# Smart_Podium_Circuit.net
KiCad netlist of a schematic drawn in Altium Designer
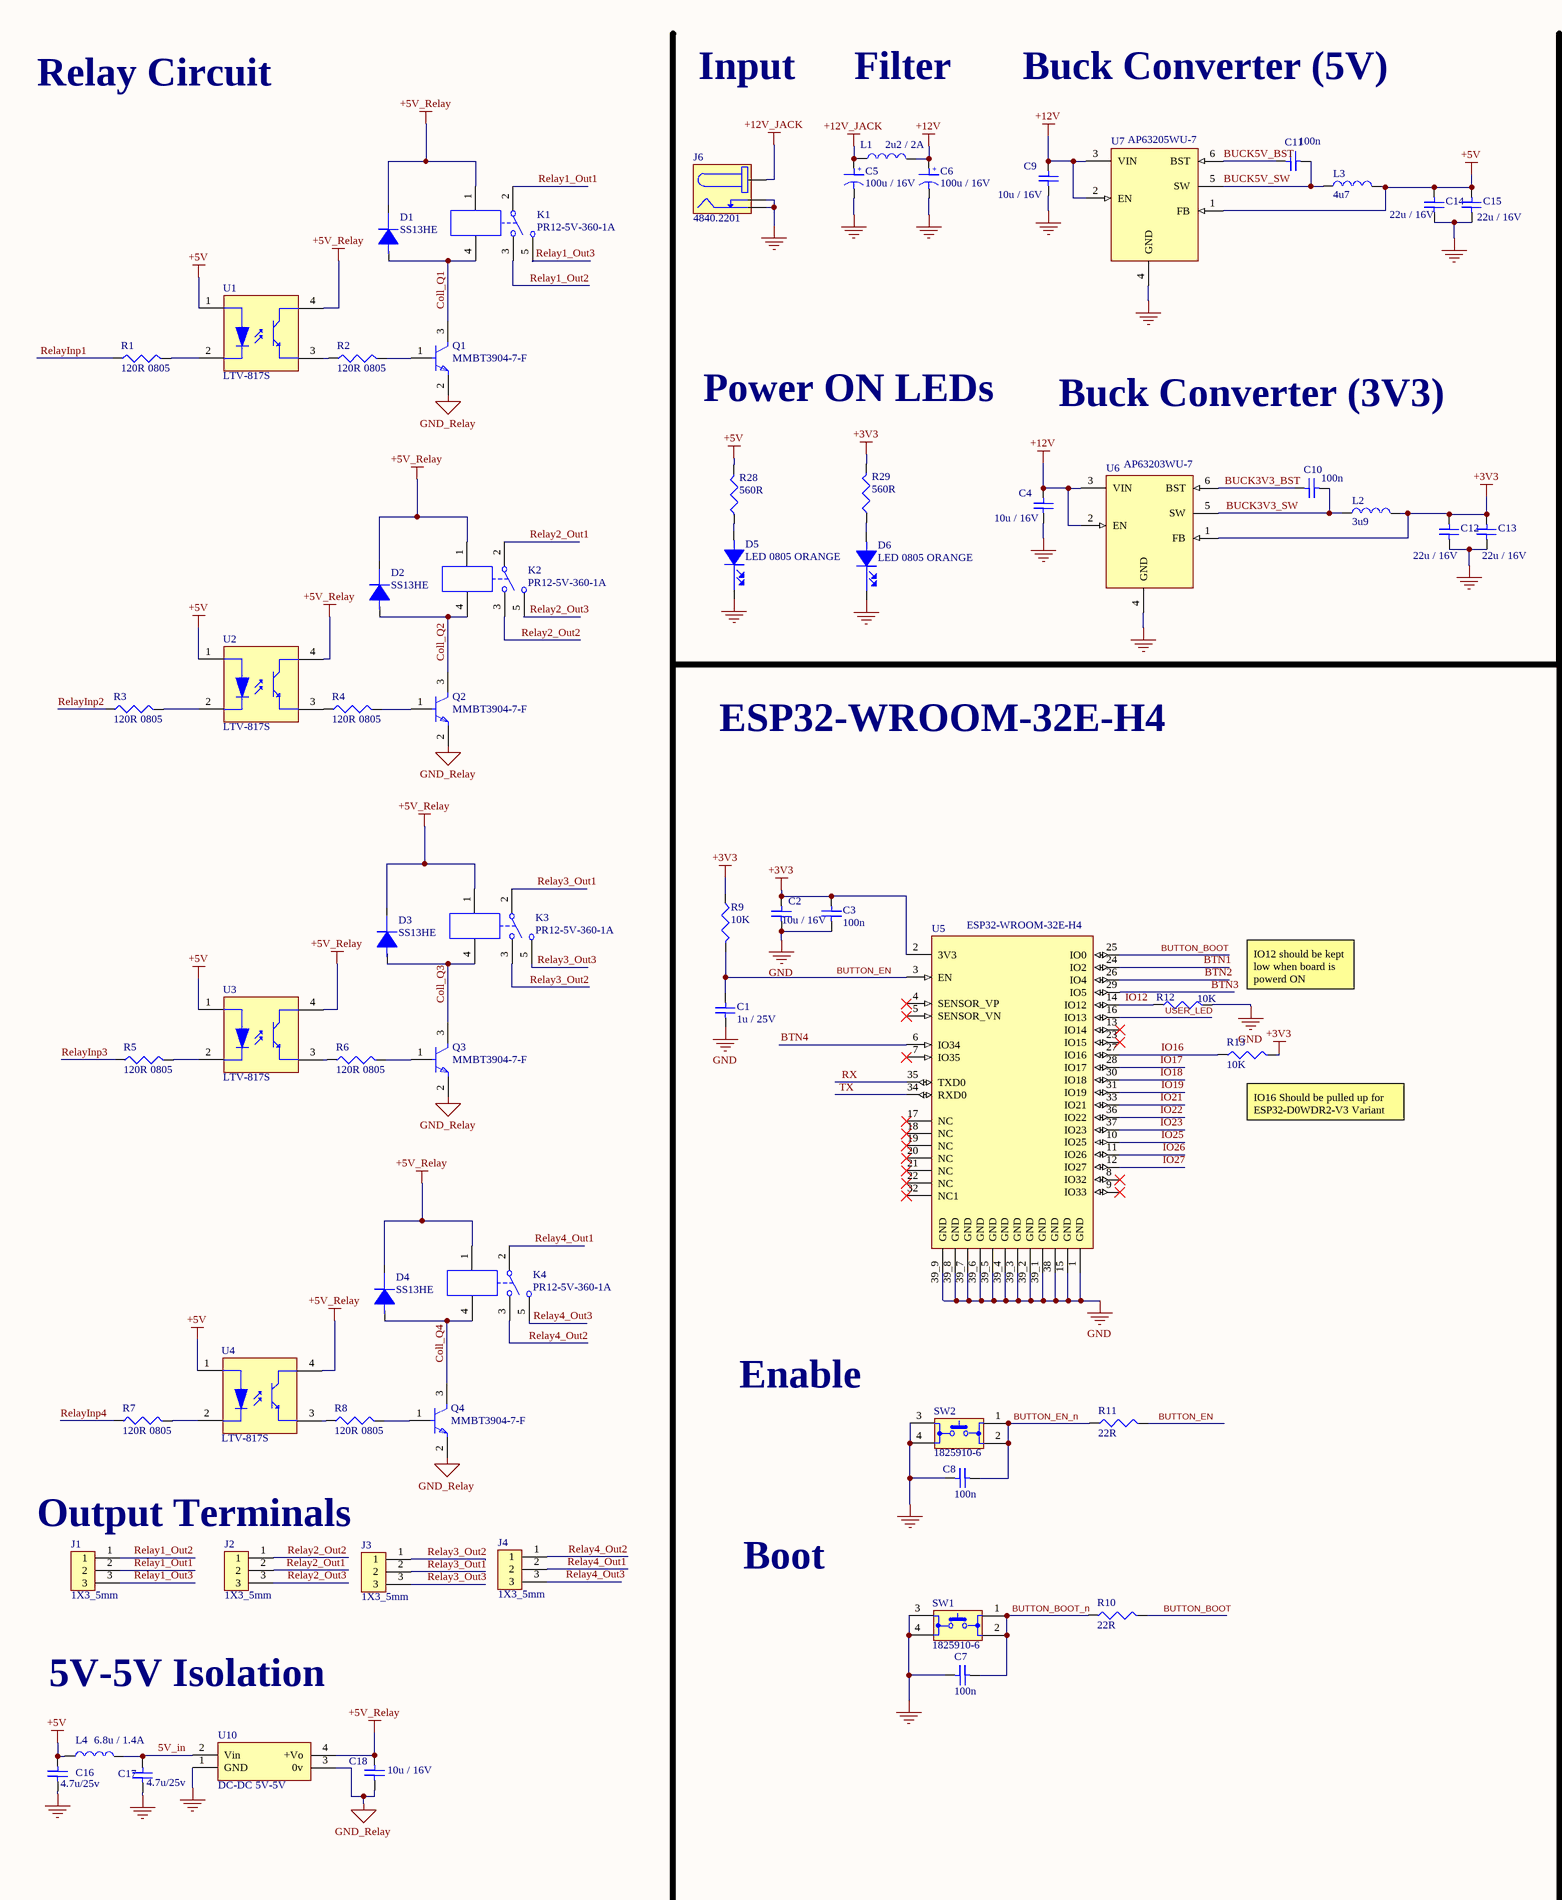
[diagram p0: Smart_Podium_Circuit.SchDoc, left]
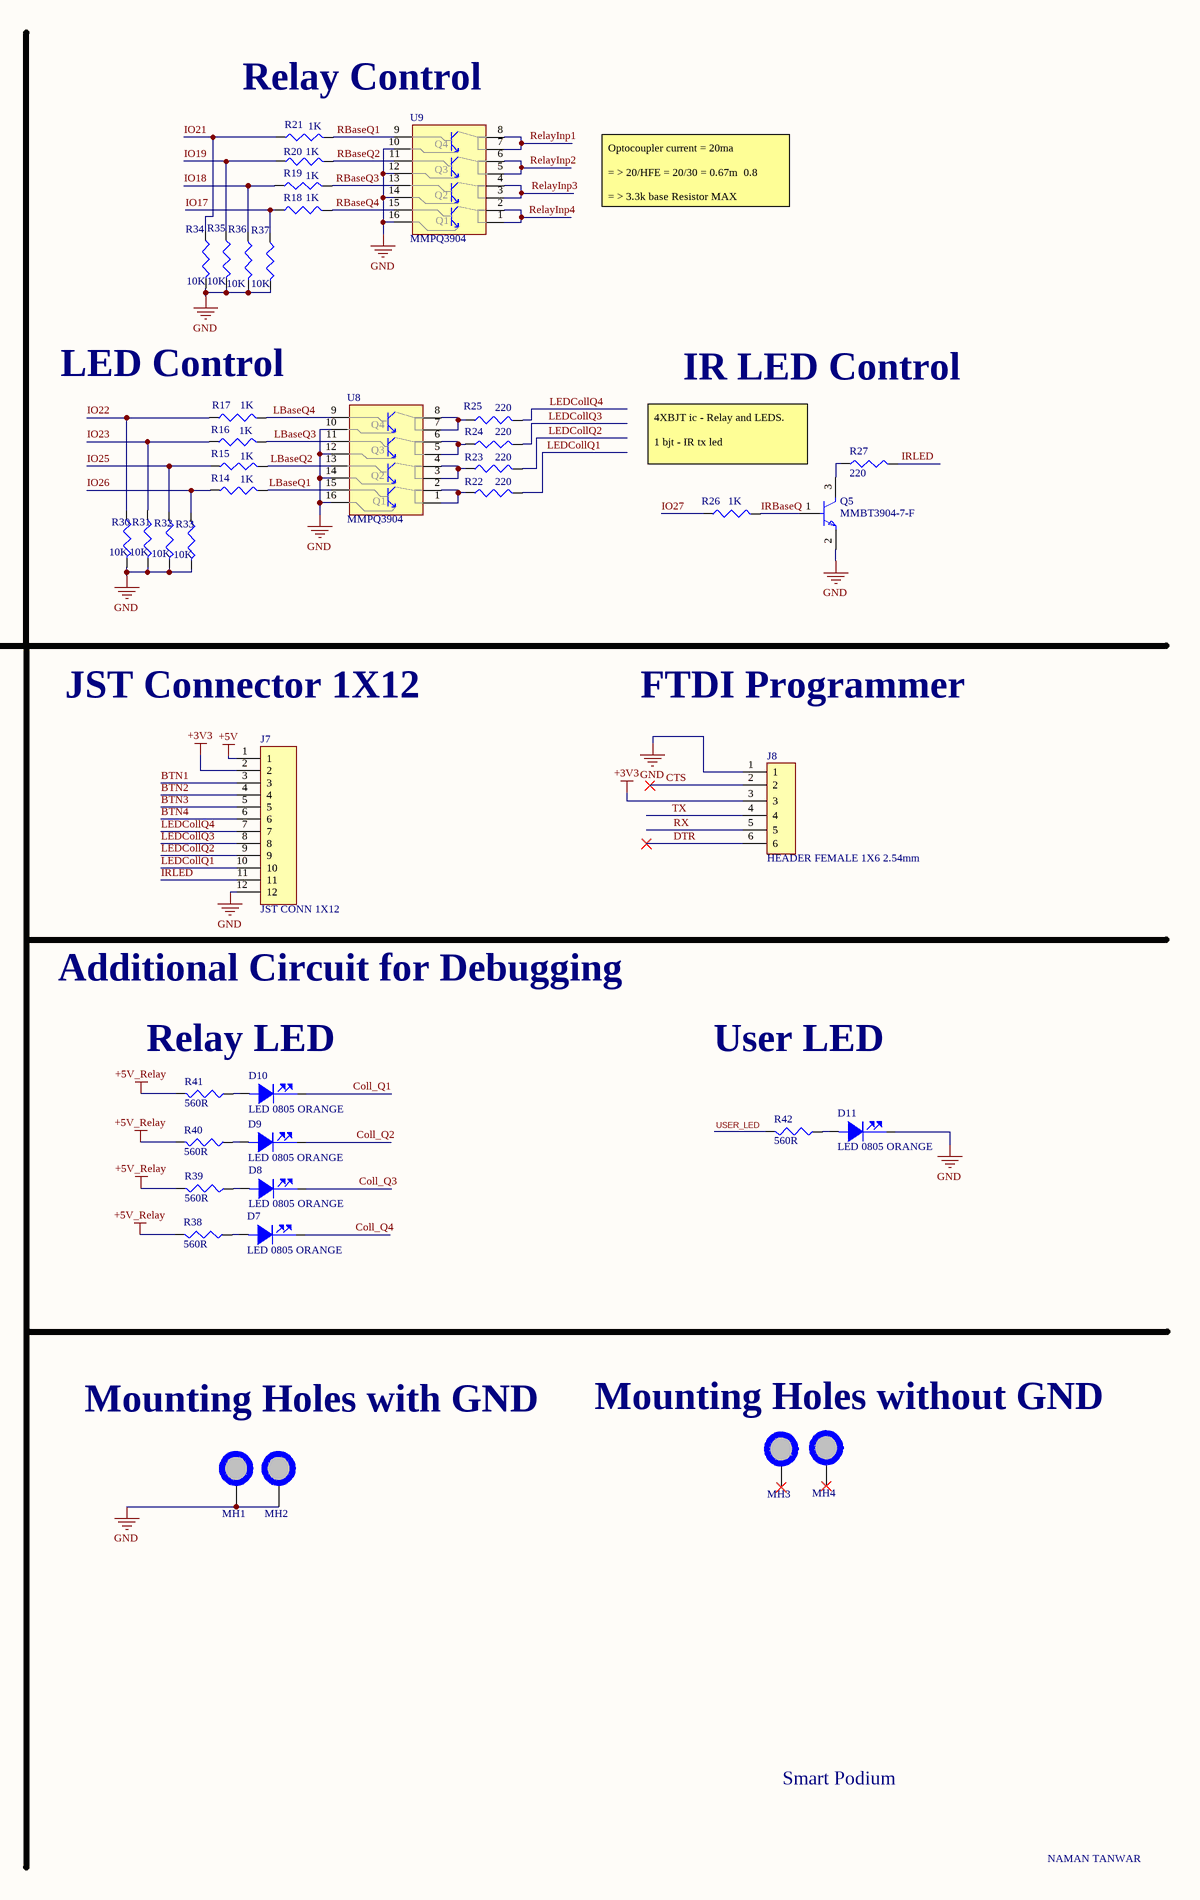
[diagram p1: Smart_Podium_Circuit.SchDoc, right]

(export (version "E")
  (design (tool "Eeschema 10.0.6"))
  (components
    (comp (ref "C1")
      (value "1u / 25V")
      (footprint "C0805")
      (description "CAP CER 1UF 25V X5R 0805")
      (fields
        (field (name "MANUFACTURER") "TDK")
        (field (name "MANUFACTURER PART NUMBER") "C2012X5R1E105K125AA")
      )
      (libsource (lib "Smart_Podium") (part "C2012X5R1E105K125AA"))
    )
    (comp (ref "C2")
      (value "10u / 16V")
      (footprint "C0805")
      (description "Cap Ceramic 10uF 16V X5R 20% SMD 0805 85°C Blister Plastic T/R")
      (fields
        (field (name "MANUFACTURER") "TDK")
        (field (name "MANUFACTURER PART NUMBER") "CGA4J1X5R1C106M125AC")
      )
      (libsource (lib "Smart_Podium") (part "CGA4J1X5R1C106M125AC"))
    )
    (comp (ref "C3")
      (value "100n")
      (footprint "C0805")
      (description "C Series 0805 0.1 uF 50 V ±20 % Tolerance X7R SMT Multilayer Ceramic Capacitor")
      (fields
        (field (name "MANUFACTURER") "TDK")
        (field (name "MANUFACTURER PART NUMBER") "C2012X7R1H104M085AA")
      )
      (libsource (lib "Smart_Podium") (part "C2012X7R1H104M085AA"))
    )
    (comp (ref "C4")
      (value "10u / 16V")
      (footprint "C0805")
      (description "Cap Ceramic 10uF 16V X5R 20% SMD 0805 85°C Blister Plastic T/R")
      (fields
        (field (name "MANUFACTURER") "TDK")
        (field (name "MANUFACTURER PART NUMBER") "CGA4J1X5R1C106M125AC")
      )
      (libsource (lib "Smart_Podium") (part "CGA4J1X5R1C106M125AC"))
    )
    (comp (ref "C5")
      (value "100u / 16V")
      (footprint "C_ALU_C_SIZE")
      (description "Cap Aluminum 100uF 16V 20% Cylindrical 0.7 Ohm 160mA 2000 hr 105°C Emboss T/R")
      (fields
        (field (name "MANUFACTURER") "Panasonic")
        (field (name "MANUFACTURER PART NUMBER") "EEE-FN1C101UR")
      )
      (libsource (lib "Smart_Podium") (part "EEE-FN1C101UR"))
    )
    (comp (ref "C6")
      (value "100u / 16V")
      (footprint "C_ALU_C_SIZE")
      (description "Cap Aluminum 100uF 16V 20% Cylindrical 0.7 Ohm 160mA 2000 hr 105°C Emboss T/R")
      (fields
        (field (name "MANUFACTURER") "Panasonic")
        (field (name "MANUFACTURER PART NUMBER") "EEE-FN1C101UR")
      )
      (libsource (lib "Smart_Podium") (part "EEE-FN1C101UR"))
    )
    (comp (ref "C7")
      (value "100n")
      (footprint "C0805")
      (description "C Series 0805 0.1 uF 50 V ±20 % Tolerance X7R SMT Multilayer Ceramic Capacitor")
      (fields
        (field (name "MANUFACTURER") "TDK")
        (field (name "MANUFACTURER PART NUMBER") "C2012X7R1H104M085AA")
      )
      (libsource (lib "Smart_Podium") (part "C2012X7R1H104M085AA"))
    )
    (comp (ref "C8")
      (value "100n")
      (footprint "C0805")
      (description "C Series 0805 0.1 uF 50 V ±20 % Tolerance X7R SMT Multilayer Ceramic Capacitor")
      (fields
        (field (name "MANUFACTURER") "TDK")
        (field (name "MANUFACTURER PART NUMBER") "C2012X7R1H104M085AA")
      )
      (libsource (lib "Smart_Podium") (part "C2012X7R1H104M085AA"))
    )
    (comp (ref "C9")
      (value "10u / 16V")
      (footprint "C0805")
      (description "Cap Ceramic 10uF 16V X5R 20% SMD 0805 85°C Blister Plastic T/R")
      (fields
        (field (name "MANUFACTURER") "TDK")
        (field (name "MANUFACTURER PART NUMBER") "CGA4J1X5R1C106M125AC")
      )
      (libsource (lib "Smart_Podium") (part "CGA4J1X5R1C106M125AC"))
    )
    (comp (ref "C10")
      (value "100n")
      (footprint "C0805")
      (description "C Series 0805 0.1 uF 50 V ±20 % Tolerance X7R SMT Multilayer Ceramic Capacitor")
      (fields
        (field (name "MANUFACTURER") "TDK")
        (field (name "MANUFACTURER PART NUMBER") "C2012X7R1H104M085AA")
      )
      (libsource (lib "Smart_Podium") (part "C2012X7R1H104M085AA"))
    )
    (comp (ref "C11")
      (value "100n")
      (footprint "C0805")
      (description "C Series 0805 0.1 uF 50 V ±20 % Tolerance X7R SMT Multilayer Ceramic Capacitor")
      (fields
        (field (name "MANUFACTURER") "TDK")
        (field (name "MANUFACTURER PART NUMBER") "C2012X7R1H104M085AA")
      )
      (libsource (lib "Smart_Podium") (part "C2012X7R1H104M085AA"))
    )
    (comp (ref "C12")
      (value "22u / 16V")
      (footprint "C0805")
      (description "Cap Ceramic 22uF 16V X5R 20% SMD 1206 85°C Cardboard T/R")
      (fields
        (field (name "MANUFACTURER") "Samsung")
        (field (name "MANUFACTURER PART NUMBER") "CL31A226MOCLNNC")
      )
      (libsource (lib "Smart_Podium") (part "CL31A226MOCLNNC"))
    )
    (comp (ref "C13")
      (value "22u / 16V")
      (footprint "C0805")
      (description "Cap Ceramic 22uF 16V X5R 20% SMD 1206 85°C Cardboard T/R")
      (fields
        (field (name "MANUFACTURER") "Samsung")
        (field (name "MANUFACTURER PART NUMBER") "CL31A226MOCLNNC")
      )
      (libsource (lib "Smart_Podium") (part "CL31A226MOCLNNC"))
    )
    (comp (ref "C14")
      (value "22u / 16V")
      (footprint "C0805")
      (description "Cap Ceramic 22uF 16V X5R 20% SMD 1206 85°C Cardboard T/R")
      (fields
        (field (name "MANUFACTURER") "Samsung")
        (field (name "MANUFACTURER PART NUMBER") "CL31A226MOCLNNC")
      )
      (libsource (lib "Smart_Podium") (part "CL31A226MOCLNNC"))
    )
    (comp (ref "C15")
      (value "22u / 16V")
      (footprint "C0805")
      (description "Cap Ceramic 22uF 16V X5R 20% SMD 1206 85°C Cardboard T/R")
      (fields
        (field (name "MANUFACTURER") "Samsung")
        (field (name "MANUFACTURER PART NUMBER") "CL31A226MOCLNNC")
      )
      (libsource (lib "Smart_Podium") (part "CL31A226MOCLNNC"))
    )
    (comp (ref "C16")
      (value "4.7u/25v")
      (footprint "C0805")
      (description "Multilayer Ceramic Capacitors (High dielectric type), 25V, 4.7 uF, ± 10 %, 0805, X5R, RoHS")
      (fields
        (field (name "MANUFACTURER") "Taiyo Yuden")
        (field (name "MANUFACTURER PART NUMBER") "TMK212ABJ475KG-T")
      )
      (libsource (lib "Smart_Podium") (part "TMK212ABJ475KG-T"))
    )
    (comp (ref "C17")
      (value "4.7u/25v")
      (footprint "C0805")
      (description "Multilayer Ceramic Capacitors (High dielectric type), 25V, 4.7 uF, ± 10 %, 0805, X5R, RoHS")
      (fields
        (field (name "MANUFACTURER") "Taiyo Yuden")
        (field (name "MANUFACTURER PART NUMBER") "TMK212ABJ475KG-T")
      )
      (libsource (lib "Smart_Podium") (part "TMK212ABJ475KG-T"))
    )
    (comp (ref "C18")
      (value "10u / 16V")
      (footprint "C0805")
      (description "Cap Ceramic 10uF 16V X5R 20% SMD 0805 85°C Blister Plastic T/R")
      (fields
        (field (name "MANUFACTURER") "TDK")
        (field (name "MANUFACTURER PART NUMBER") "CGA4J1X5R1C106M125AC")
      )
      (libsource (lib "Smart_Podium") (part "CGA4J1X5R1C106M125AC"))
    )
    (comp (ref "D1")
      (value "SS13HE")
      (footprint "SOD323HE")
      (description "SS13HE Series 30 V 1 A Surface Mount Schottky Barrier Rectifier - SOD-323HE")
      (fields (field (name "MANUFACTURER") "ON Semiconductor / Fairchild"))
      (libsource (lib "Smart_Podium") (part "SS13HE"))
    )
    (comp (ref "D2")
      (value "SS13HE")
      (footprint "SOD323HE")
      (description "SS13HE Series 30 V 1 A Surface Mount Schottky Barrier Rectifier - SOD-323HE")
      (fields (field (name "MANUFACTURER") "ON Semiconductor / Fairchild"))
      (libsource (lib "Smart_Podium") (part "SS13HE"))
    )
    (comp (ref "D3")
      (value "SS13HE")
      (footprint "SOD323HE")
      (description "SS13HE Series 30 V 1 A Surface Mount Schottky Barrier Rectifier - SOD-323HE")
      (fields (field (name "MANUFACTURER") "ON Semiconductor / Fairchild"))
      (libsource (lib "Smart_Podium") (part "SS13HE"))
    )
    (comp (ref "D4")
      (value "SS13HE")
      (footprint "SOD323HE")
      (description "SS13HE Series 30 V 1 A Surface Mount Schottky Barrier Rectifier - SOD-323HE")
      (fields (field (name "MANUFACTURER") "ON Semiconductor / Fairchild"))
      (libsource (lib "Smart_Podium") (part "SS13HE"))
    )
    (comp (ref "D5")
      (value "LED 0805 ORANGE")
      (footprint "LED_0805")
      (description "Orange LED 0805 Vf = 2V, 20mA")
      (fields
        (field (name "MANUFACTURER") "Osram Opto")
        (field (name "MANUFACTURER PART NUMBER") "LOR976-PS-1")
      )
      (libsource (lib "Smart_Podium") (part "LOR976-PS-1"))
    )
    (comp (ref "D6")
      (value "LED 0805 ORANGE")
      (footprint "LED_0805")
      (description "Orange LED 0805 Vf = 2V, 20mA")
      (fields
        (field (name "MANUFACTURER") "Osram Opto")
        (field (name "MANUFACTURER PART NUMBER") "LOR976-PS-1")
      )
      (libsource (lib "Smart_Podium") (part "LOR976-PS-1"))
    )
    (comp (ref "D7")
      (value "LED 0805 ORANGE")
      (footprint "LED_0805")
      (description "Orange LED 0805 Vf = 2V, 20mA")
      (fields
        (field (name "MANUFACTURER") "Osram Opto")
        (field (name "MANUFACTURER PART NUMBER") "LOR976-PS-1")
      )
      (libsource (lib "Smart_Podium") (part "LOR976-PS-1"))
    )
    (comp (ref "D8")
      (value "LED 0805 ORANGE")
      (footprint "LED_0805")
      (description "Orange LED 0805 Vf = 2V, 20mA")
      (fields
        (field (name "MANUFACTURER") "Osram Opto")
        (field (name "MANUFACTURER PART NUMBER") "LOR976-PS-1")
      )
      (libsource (lib "Smart_Podium") (part "LOR976-PS-1"))
    )
    (comp (ref "D9")
      (value "LED 0805 ORANGE")
      (footprint "LED_0805")
      (description "Orange LED 0805 Vf = 2V, 20mA")
      (fields
        (field (name "MANUFACTURER") "Osram Opto")
        (field (name "MANUFACTURER PART NUMBER") "LOR976-PS-1")
      )
      (libsource (lib "Smart_Podium") (part "LOR976-PS-1"))
    )
    (comp (ref "D10")
      (value "LED 0805 ORANGE")
      (footprint "LED_0805")
      (description "Orange LED 0805 Vf = 2V, 20mA")
      (fields
        (field (name "MANUFACTURER") "Osram Opto")
        (field (name "MANUFACTURER PART NUMBER") "LOR976-PS-1")
      )
      (libsource (lib "Smart_Podium") (part "LOR976-PS-1"))
    )
    (comp (ref "D11")
      (value "LED 0805 ORANGE")
      (footprint "LED_0805")
      (description "Orange LED 0805 Vf = 2V, 20mA")
      (fields
        (field (name "MANUFACTURER") "Osram Opto")
        (field (name "MANUFACTURER PART NUMBER") "LOR976-PS-1")
      )
      (libsource (lib "Smart_Podium") (part "LOR976-PS-1"))
    )
    (comp (ref "J1")
      (value "1X3_5mm")
      (footprint "SSCREW_CONN_5MM_1X3")
      (description "Terminal Block Header 3 Position Top Screw 0.197\" (5.00mm) PC Pins")
      (fields
        (field (name "MANUFACTURER") "Phoenix Contact")
        (field (name "MANUFACTURER PART NUMBER") "1935174")
      )
      (libsource (lib "Smart_Podium") (part "1935174"))
    )
    (comp (ref "J2")
      (value "1X3_5mm")
      (footprint "SSCREW_CONN_5MM_1X3")
      (description "Terminal Block Header 3 Position Top Screw 0.197\" (5.00mm) PC Pins")
      (fields
        (field (name "MANUFACTURER") "Phoenix Contact")
        (field (name "MANUFACTURER PART NUMBER") "1935174")
      )
      (libsource (lib "Smart_Podium") (part "1935174"))
    )
    (comp (ref "J3")
      (value "1X3_5mm")
      (footprint "SSCREW_CONN_5MM_1X3")
      (description "Terminal Block Header 3 Position Top Screw 0.197\" (5.00mm) PC Pins")
      (fields
        (field (name "MANUFACTURER") "Phoenix Contact")
        (field (name "MANUFACTURER PART NUMBER") "1935174")
      )
      (libsource (lib "Smart_Podium") (part "1935174"))
    )
    (comp (ref "J4")
      (value "1X3_5mm")
      (footprint "SSCREW_CONN_5MM_1X3")
      (description "Terminal Block Header 3 Position Top Screw 0.197\" (5.00mm) PC Pins")
      (fields
        (field (name "MANUFACTURER") "Phoenix Contact")
        (field (name "MANUFACTURER PART NUMBER") "1935174")
      )
      (libsource (lib "Smart_Podium") (part "1935174"))
    )
    (comp (ref "J6")
      (value "4840.2201")
      (footprint "DC_JACK")
      (description "DC Connector Socket 6x2mm 2-Pole 12VDC 0.5A 500VDC Dielectric Solder Term PCB Mt")
      (fields (field (name "MANUFACTURER") "Schurter"))
      (libsource (lib "Smart_Podium") (part "4840.2201"))
    )
    (comp (ref "J7")
      (value "JST CONN 1X12")
      (footprint "FP-B12B-XH-A_LF_SN-MFG")
      (description "CONN HEADER VERT 12POS 2.5MM")
      (fields (field (name "MANUFACTURER PART NUMBER") "B12B-XH-A(LF)(SN)"))
      (libsource (lib "Smart_Podium") (part "B12B-XH-A(LF)(SN)"))
    )
    (comp (ref "J8")
      (value "HEADER FEMALE 1X6 2.54mm")
      (footprint "Header_Female_1x6_2.54mm")
      (description "Female, 6 C, Straight, .100\"CC; 3.20mm Tail, No Mt. 100u\" Tin; PBT, Phos Bronze, 105 C")
      (fields
        (field (name "MANUFACTURER") "Sullins")
        (field (name "MANUFACTURER PART NUMBER") "PPTC061LFBN-RC")
      )
      (libsource (lib "Smart_Podium") (part "PPTC061LFBN-RC"))
    )
    (comp (ref "K1")
      (value "PR12-5V-360-1A")
      (footprint "Relay_SPST")
      (description "Power Relay 5VDC 15A SPST-NO(19mm 15.5mm 15.8mm) THT")
      (fields (field (name "MANUFACTURER") "CUI Devices"))
      (libsource (lib "Smart_Podium") (part "PR12-5V-360-1A"))
    )
    (comp (ref "K2")
      (value "PR12-5V-360-1A")
      (footprint "Relay_SPST")
      (description "Power Relay 5VDC 15A SPST-NO(19mm 15.5mm 15.8mm) THT")
      (fields (field (name "MANUFACTURER") "CUI Devices"))
      (libsource (lib "Smart_Podium") (part "PR12-5V-360-1A"))
    )
    (comp (ref "K3")
      (value "PR12-5V-360-1A")
      (footprint "Relay_SPST")
      (description "Power Relay 5VDC 15A SPST-NO(19mm 15.5mm 15.8mm) THT")
      (fields (field (name "MANUFACTURER") "CUI Devices"))
      (libsource (lib "Smart_Podium") (part "PR12-5V-360-1A"))
    )
    (comp (ref "K4")
      (value "PR12-5V-360-1A")
      (footprint "Relay_SPST")
      (description "Power Relay 5VDC 15A SPST-NO(19mm 15.5mm 15.8mm) THT")
      (fields (field (name "MANUFACTURER") "CUI Devices"))
      (libsource (lib "Smart_Podium") (part "PR12-5V-360-1A"))
    )
    (comp (ref "L1")
      (value "2u2 / 2A")
      (footprint "C1210_IND")
      (description "Inductor RF Chip Wirewound 2.2uH 20% 100KHz 1.13A 0.104Ohm DCR 1210 T/R")
      (fields
        (field (name "MANUFACTURER") "KEMET")
        (field (name "MANUFACTURER PART NUMBER") "L1210R2R2MDWIT")
      )
      (libsource (lib "Smart_Podium") (part "L1210R2R2MDWIT"))
    )
    (comp (ref "L2")
      (value "3u9")
      (footprint "3u9_IND_NON_STANDARD")
      (description "Inductor Power Shielded Wirewound 3.9uH 30% 100KHz Ferrite 3.4A 0.047Ohm DCR Automotive T/R")
      (fields
        (field (name "MANUFACTURER") "Bourns")
        (field (name "MANUFACTURER PART NUMBER") "SRR4828A-3R9Y")
      )
      (libsource (lib "Smart_Podium") (part "SRR4828A-3R9Y"))
    )
    (comp (ref "L3")
      (value "4u7")
      (footprint "4u7_IND_NON_STANDARD")
      (description "Inductor Power Shielded Wirewound 4.7uH 30% 100KHz Ferrite 3A 0.054Ohm DCR Automotive T/R")
      (fields
        (field (name "MANUFACTURER") "Bourns")
        (field (name "MANUFACTURER PART NUMBER") "SRR4828A-4R7Y")
      )
      (libsource (lib "Smart_Podium") (part "SRR4828A-4R7Y"))
    )
    (comp (ref "L4")
      (value "6.8u / 1.4A")
      (footprint "C1210_IND")
      (description "Inductor Power Shielded Thin Film 6.8uH 20% 1MHz Metal 1.4A 0.26Ohm DCR 1210 Automotive T/R")
      (fields
        (field (name "MANUFACTURER") "TDK")
        (field (name "MANUFACTURER PART NUMBER") "TFM322512ALMA6R8MTAA")
      )
      (libsource (lib "Smart_Podium") (part "TFM322512ALMA6R8MTAA"))
    )
    (comp (ref "MH1")
      (value "MH_7.4MMC_3.2MMD")
      (footprint "MH_7.4MMC_3.2MMD")
      (description "Mounting Hole 7.4mm Diameter, 3.2mm Drill")
      (libsource (lib "Smart_Podium") (part "MH_7.4MMC_3.2MMD"))
    )
    (comp (ref "MH2")
      (value "MH_7.4MMC_3.2MMD")
      (footprint "MH_7.4MMC_3.2MMD")
      (description "Mounting Hole 7.4mm Diameter, 3.2mm Drill")
      (libsource (lib "Smart_Podium") (part "MH_7.4MMC_3.2MMD"))
    )
    (comp (ref "MH3")
      (value "MH_7.4MMNC_3.2MMD")
      (footprint "MH_7.4MMC_3.2MMD_NON_COPPER_NPTH")
      (description "Mounting Hole Non Copper 7.4mm Diameter, 3.2mm Drill NPTH")
      (libsource (lib "Smart_Podium") (part "MH_7.4MMNC_3.2MMD"))
    )
    (comp (ref "MH4")
      (value "MH_7.4MMNC_3.2MMD")
      (footprint "MH_7.4MMC_3.2MMD_NON_COPPER_NPTH")
      (description "Mounting Hole Non Copper 7.4mm Diameter, 3.2mm Drill NPTH")
      (libsource (lib "Smart_Podium") (part "MH_7.4MMNC_3.2MMD"))
    )
    (comp (ref "Q1")
      (value "MMBT3904-7-F")
      (footprint "FP-SOT23-IPC_A")
      (description "TRANS NPN 40V 0.2A SMD SOT23-3")
      (libsource (lib "Altium Content Vault") (part "b44e953556f554d0102664c7d152cb4"))
    )
    (comp (ref "Q2")
      (value "MMBT3904-7-F")
      (footprint "FP-SOT23-IPC_A")
      (description "TRANS NPN 40V 0.2A SMD SOT23-3")
      (libsource (lib "Altium Content Vault") (part "b44e953556f554d0102664c7d152cb4"))
    )
    (comp (ref "Q3")
      (value "MMBT3904-7-F")
      (footprint "FP-SOT23-IPC_A")
      (description "TRANS NPN 40V 0.2A SMD SOT23-3")
      (libsource (lib "Altium Content Vault") (part "b44e953556f554d0102664c7d152cb4"))
    )
    (comp (ref "Q4")
      (value "MMBT3904-7-F")
      (footprint "FP-SOT23-IPC_A")
      (description "TRANS NPN 40V 0.2A SMD SOT23-3")
      (libsource (lib "Altium Content Vault") (part "b44e953556f554d0102664c7d152cb4"))
    )
    (comp (ref "Q5")
      (value "MMBT3904-7-F")
      (footprint "FP-SOT23-IPC_A")
      (description "TRANS NPN 40V 0.2A SMD SOT23-3")
      (libsource (lib "Altium Content Vault") (part "b44e953556f554d0102664c7d152cb4"))
    )
    (comp (ref "R1")
      (value "120R 0805")
      (footprint "R0805")
      (description "Res Thin Film 0805 120 Ohm 0.5% 1/10W ±25ppm/°C Molded SMD SMD Paper T/R")
      (fields
        (field (name "MANUFACTURER") "Stackpole Electronics")
        (field (name "MANUFACTURER PART NUMBER") "RNCF0805DTE120R")
      )
      (libsource (lib "Smart_Podium") (part "RNCF0805DTE120R"))
    )
    (comp (ref "R2")
      (value "120R 0805")
      (footprint "R0805")
      (description "Res Thin Film 0805 120 Ohm 0.5% 1/10W ±25ppm/°C Molded SMD SMD Paper T/R")
      (fields
        (field (name "MANUFACTURER") "Stackpole Electronics")
        (field (name "MANUFACTURER PART NUMBER") "RNCF0805DTE120R")
      )
      (libsource (lib "Smart_Podium") (part "RNCF0805DTE120R"))
    )
    (comp (ref "R3")
      (value "120R 0805")
      (footprint "R0805")
      (description "Res Thin Film 0805 120 Ohm 0.5% 1/10W ±25ppm/°C Molded SMD SMD Paper T/R")
      (fields
        (field (name "MANUFACTURER") "Stackpole Electronics")
        (field (name "MANUFACTURER PART NUMBER") "RNCF0805DTE120R")
      )
      (libsource (lib "Smart_Podium") (part "RNCF0805DTE120R"))
    )
    (comp (ref "R4")
      (value "120R 0805")
      (footprint "R0805")
      (description "Res Thin Film 0805 120 Ohm 0.5% 1/10W ±25ppm/°C Molded SMD SMD Paper T/R")
      (fields
        (field (name "MANUFACTURER") "Stackpole Electronics")
        (field (name "MANUFACTURER PART NUMBER") "RNCF0805DTE120R")
      )
      (libsource (lib "Smart_Podium") (part "RNCF0805DTE120R"))
    )
    (comp (ref "R5")
      (value "120R 0805")
      (footprint "R0805")
      (description "Res Thin Film 0805 120 Ohm 0.5% 1/10W ±25ppm/°C Molded SMD SMD Paper T/R")
      (fields
        (field (name "MANUFACTURER") "Stackpole Electronics")
        (field (name "MANUFACTURER PART NUMBER") "RNCF0805DTE120R")
      )
      (libsource (lib "Smart_Podium") (part "RNCF0805DTE120R"))
    )
    (comp (ref "R6")
      (value "120R 0805")
      (footprint "R0805")
      (description "Res Thin Film 0805 120 Ohm 0.5% 1/10W ±25ppm/°C Molded SMD SMD Paper T/R")
      (fields
        (field (name "MANUFACTURER") "Stackpole Electronics")
        (field (name "MANUFACTURER PART NUMBER") "RNCF0805DTE120R")
      )
      (libsource (lib "Smart_Podium") (part "RNCF0805DTE120R"))
    )
    (comp (ref "R7")
      (value "120R 0805")
      (footprint "R0805")
      (description "Res Thin Film 0805 120 Ohm 0.5% 1/10W ±25ppm/°C Molded SMD SMD Paper T/R")
      (fields
        (field (name "MANUFACTURER") "Stackpole Electronics")
        (field (name "MANUFACTURER PART NUMBER") "RNCF0805DTE120R")
      )
      (libsource (lib "Smart_Podium") (part "RNCF0805DTE120R"))
    )
    (comp (ref "R8")
      (value "120R 0805")
      (footprint "R0805")
      (description "Res Thin Film 0805 120 Ohm 0.5% 1/10W ±25ppm/°C Molded SMD SMD Paper T/R")
      (fields
        (field (name "MANUFACTURER") "Stackpole Electronics")
        (field (name "MANUFACTURER PART NUMBER") "RNCF0805DTE120R")
      )
      (libsource (lib "Smart_Podium") (part "RNCF0805DTE120R"))
    )
    (comp (ref "R9")
      (value "10K")
      (footprint "R0805")
      (description "Res Thick Film 0805 10K Ohm 1% 0.125W(1/8W) +/-100ppm/C Epoxy Pad SMD T/R")
      (fields
        (field (name "MANUFACTURER") "Yageo")
        (field (name "MANUFACTURER PART NUMBER") "RC0805FR-0710KL")
      )
      (libsource (lib "Smart_Podium") (part "RC0805FR-0710KL"))
    )
    (comp (ref "R10")
      (value "22R")
      (footprint "R0805")
      (description "Res Thick Film 0805 22 Ohm 1% 0.125W(1/8W) ±100ppm/C Pad SMD T/R")
      (fields
        (field (name "MANUFACTURER") "Yageo")
        (field (name "MANUFACTURER PART NUMBER") "RC0805FR-0722RL")
      )
      (libsource (lib "20Pin_Arduino_Project_V1I1") (part "RC0805FR-0722RL"))
    )
    (comp (ref "R11")
      (value "22R")
      (footprint "R0805")
      (description "Res Thick Film 0805 22 Ohm 1% 0.125W(1/8W) ±100ppm/C Pad SMD T/R")
      (fields
        (field (name "MANUFACTURER") "Yageo")
        (field (name "MANUFACTURER PART NUMBER") "RC0805FR-0722RL")
      )
      (libsource (lib "20Pin_Arduino_Project_V1I1") (part "RC0805FR-0722RL"))
    )
    (comp (ref "R12")
      (value "10K")
      (footprint "R0805")
      (description "Res Thick Film 0805 10K Ohm 1% 0.125W(1/8W) +/-100ppm/C Epoxy Pad SMD T/R")
      (fields
        (field (name "MANUFACTURER") "Yageo")
        (field (name "MANUFACTURER PART NUMBER") "RC0805FR-0710KL")
      )
      (libsource (lib "Smart_Podium") (part "RC0805FR-0710KL"))
    )
    (comp (ref "R13")
      (value "10K")
      (footprint "R0805")
      (description "Res Thick Film 0805 10K Ohm 1% 0.125W(1/8W) +/-100ppm/C Epoxy Pad SMD T/R")
      (fields
        (field (name "MANUFACTURER") "Yageo")
        (field (name "MANUFACTURER PART NUMBER") "RC0805FR-0710KL")
      )
      (libsource (lib "Smart_Podium") (part "RC0805FR-0710KL"))
    )
    (comp (ref "R14")
      (value "1K")
      (footprint "R0805")
      (description "Res Thin Film 0805 1K Ohm 1% 0.25W(1/4W) ±100ppm/C Sulfur Resistant Pad SMD T/R")
      (fields
        (field (name "MANUFACTURER") "Stackpole Electronics")
        (field (name "MANUFACTURER PART NUMBER") "RNCP0805FTD1K00")
      )
      (libsource (lib "Smart_Podium") (part "RNCP0805FTD1K00"))
    )
    (comp (ref "R15")
      (value "1K")
      (footprint "R0805")
      (description "Res Thin Film 0805 1K Ohm 1% 0.25W(1/4W) ±100ppm/C Sulfur Resistant Pad SMD T/R")
      (fields
        (field (name "MANUFACTURER") "Stackpole Electronics")
        (field (name "MANUFACTURER PART NUMBER") "RNCP0805FTD1K00")
      )
      (libsource (lib "Smart_Podium") (part "RNCP0805FTD1K00"))
    )
    (comp (ref "R16")
      (value "1K")
      (footprint "R0805")
      (description "Res Thin Film 0805 1K Ohm 1% 0.25W(1/4W) ±100ppm/C Sulfur Resistant Pad SMD T/R")
      (fields
        (field (name "MANUFACTURER") "Stackpole Electronics")
        (field (name "MANUFACTURER PART NUMBER") "RNCP0805FTD1K00")
      )
      (libsource (lib "Smart_Podium") (part "RNCP0805FTD1K00"))
    )
    (comp (ref "R17")
      (value "1K")
      (footprint "R0805")
      (description "Res Thin Film 0805 1K Ohm 1% 0.25W(1/4W) ±100ppm/C Sulfur Resistant Pad SMD T/R")
      (fields
        (field (name "MANUFACTURER") "Stackpole Electronics")
        (field (name "MANUFACTURER PART NUMBER") "RNCP0805FTD1K00")
      )
      (libsource (lib "Smart_Podium") (part "RNCP0805FTD1K00"))
    )
    (comp (ref "R18")
      (value "1K")
      (footprint "R0805")
      (description "Res Thin Film 0805 1K Ohm 1% 0.25W(1/4W) ±100ppm/C Sulfur Resistant Pad SMD T/R")
      (fields
        (field (name "MANUFACTURER") "Stackpole Electronics")
        (field (name "MANUFACTURER PART NUMBER") "RNCP0805FTD1K00")
      )
      (libsource (lib "Smart_Podium") (part "RNCP0805FTD1K00"))
    )
    (comp (ref "R19")
      (value "1K")
      (footprint "R0805")
      (description "Res Thin Film 0805 1K Ohm 1% 0.25W(1/4W) ±100ppm/C Sulfur Resistant Pad SMD T/R")
      (fields
        (field (name "MANUFACTURER") "Stackpole Electronics")
        (field (name "MANUFACTURER PART NUMBER") "RNCP0805FTD1K00")
      )
      (libsource (lib "Smart_Podium") (part "RNCP0805FTD1K00"))
    )
    (comp (ref "R20")
      (value "1K")
      (footprint "R0805")
      (description "Res Thin Film 0805 1K Ohm 1% 0.25W(1/4W) ±100ppm/C Sulfur Resistant Pad SMD T/R")
      (fields
        (field (name "MANUFACTURER") "Stackpole Electronics")
        (field (name "MANUFACTURER PART NUMBER") "RNCP0805FTD1K00")
      )
      (libsource (lib "Smart_Podium") (part "RNCP0805FTD1K00"))
    )
    (comp (ref "R21")
      (value "1K")
      (footprint "R0805")
      (description "Res Thin Film 0805 1K Ohm 1% 0.25W(1/4W) ±100ppm/C Sulfur Resistant Pad SMD T/R")
      (fields
        (field (name "MANUFACTURER") "Stackpole Electronics")
        (field (name "MANUFACTURER PART NUMBER") "RNCP0805FTD1K00")
      )
      (libsource (lib "Smart_Podium") (part "RNCP0805FTD1K00"))
    )
    (comp (ref "R22")
      (value "220")
      (footprint "R0805")
      (description "Res Thick Film 0805 220 Ohm 5% 0.125W(1/8W) ±100ppm/C Pad SMD T/R")
      (fields
        (field (name "MANUFACTURER") "Yageo")
        (field (name "MANUFACTURER PART NUMBER") "RC0805JR-13220RL")
      )
      (libsource (lib "Smart_Podium") (part "RC0805JR-13220RL"))
    )
    (comp (ref "R23")
      (value "220")
      (footprint "R0805")
      (description "Res Thick Film 0805 220 Ohm 5% 0.125W(1/8W) ±100ppm/C Pad SMD T/R")
      (fields
        (field (name "MANUFACTURER") "Yageo")
        (field (name "MANUFACTURER PART NUMBER") "RC0805JR-13220RL")
      )
      (libsource (lib "Smart_Podium") (part "RC0805JR-13220RL"))
    )
    (comp (ref "R24")
      (value "220")
      (footprint "R0805")
      (description "Res Thick Film 0805 220 Ohm 5% 0.125W(1/8W) ±100ppm/C Pad SMD T/R")
      (fields
        (field (name "MANUFACTURER") "Yageo")
        (field (name "MANUFACTURER PART NUMBER") "RC0805JR-13220RL")
      )
      (libsource (lib "Smart_Podium") (part "RC0805JR-13220RL"))
    )
    (comp (ref "R25")
      (value "220")
      (footprint "R0805")
      (description "Res Thick Film 0805 220 Ohm 5% 0.125W(1/8W) ±100ppm/C Pad SMD T/R")
      (fields
        (field (name "MANUFACTURER") "Yageo")
        (field (name "MANUFACTURER PART NUMBER") "RC0805JR-13220RL")
      )
      (libsource (lib "Smart_Podium") (part "RC0805JR-13220RL"))
    )
    (comp (ref "R26")
      (value "1K")
      (footprint "R0805")
      (description "Res Thin Film 0805 1K Ohm 1% 0.25W(1/4W) ±100ppm/C Sulfur Resistant Pad SMD T/R")
      (fields
        (field (name "MANUFACTURER") "Stackpole Electronics")
        (field (name "MANUFACTURER PART NUMBER") "RNCP0805FTD1K00")
      )
      (libsource (lib "Smart_Podium") (part "RNCP0805FTD1K00"))
    )
    (comp (ref "R27")
      (value "220")
      (footprint "R0805")
      (description "Res Thick Film 0805 220 Ohm 5% 0.125W(1/8W) ±100ppm/C Pad SMD T/R")
      (fields
        (field (name "MANUFACTURER") "Yageo")
        (field (name "MANUFACTURER PART NUMBER") "RC0805JR-13220RL")
      )
      (libsource (lib "Smart_Podium") (part "RC0805JR-13220RL"))
    )
    (comp (ref "R28")
      (value "560R")
      (footprint "R0805")
      (description "Res General Purpose Thick Film 0805 560 Ohm 1% 1/8W ±100ppm/°C Molded Paper T/R")
      (fields
        (field (name "MANUFACTURER") "Yageo")
        (field (name "MANUFACTURER PART NUMBER") "RC0805FR-07560RL")
      )
      (libsource (lib "Smart_Podium") (part "RC0805FR-07560RL"))
    )
    (comp (ref "R29")
      (value "560R")
      (footprint "R0805")
      (description "Res General Purpose Thick Film 0805 560 Ohm 1% 1/8W ±100ppm/°C Molded Paper T/R")
      (fields
        (field (name "MANUFACTURER") "Yageo")
        (field (name "MANUFACTURER PART NUMBER") "RC0805FR-07560RL")
      )
      (libsource (lib "Smart_Podium") (part "RC0805FR-07560RL"))
    )
    (comp (ref "R30")
      (value "10K")
      (footprint "R0805")
      (description "Res Thick Film 0805 10K Ohm 1% 0.125W(1/8W) +/-100ppm/C Epoxy Pad SMD T/R")
      (fields
        (field (name "MANUFACTURER") "Yageo")
        (field (name "MANUFACTURER PART NUMBER") "RC0805FR-0710KL")
      )
      (libsource (lib "Smart_Podium") (part "RC0805FR-0710KL"))
    )
    (comp (ref "R31")
      (value "10K")
      (footprint "R0805")
      (description "Res Thick Film 0805 10K Ohm 1% 0.125W(1/8W) +/-100ppm/C Epoxy Pad SMD T/R")
      (fields
        (field (name "MANUFACTURER") "Yageo")
        (field (name "MANUFACTURER PART NUMBER") "RC0805FR-0710KL")
      )
      (libsource (lib "Smart_Podium") (part "RC0805FR-0710KL"))
    )
    (comp (ref "R32")
      (value "10K")
      (footprint "R0805")
      (description "Res Thick Film 0805 10K Ohm 1% 0.125W(1/8W) +/-100ppm/C Epoxy Pad SMD T/R")
      (fields
        (field (name "MANUFACTURER") "Yageo")
        (field (name "MANUFACTURER PART NUMBER") "RC0805FR-0710KL")
      )
      (libsource (lib "Smart_Podium") (part "RC0805FR-0710KL"))
    )
    (comp (ref "R33")
      (value "10K")
      (footprint "R0805")
      (description "Res Thick Film 0805 10K Ohm 1% 0.125W(1/8W) +/-100ppm/C Epoxy Pad SMD T/R")
      (fields
        (field (name "MANUFACTURER") "Yageo")
        (field (name "MANUFACTURER PART NUMBER") "RC0805FR-0710KL")
      )
      (libsource (lib "Smart_Podium") (part "RC0805FR-0710KL"))
    )
    (comp (ref "R34")
      (value "10K")
      (footprint "R0805")
      (description "Res Thick Film 0805 10K Ohm 1% 0.125W(1/8W) +/-100ppm/C Epoxy Pad SMD T/R")
      (fields
        (field (name "MANUFACTURER") "Yageo")
        (field (name "MANUFACTURER PART NUMBER") "RC0805FR-0710KL")
      )
      (libsource (lib "Smart_Podium") (part "RC0805FR-0710KL"))
    )
    (comp (ref "R35")
      (value "10K")
      (footprint "R0805")
      (description "Res Thick Film 0805 10K Ohm 1% 0.125W(1/8W) +/-100ppm/C Epoxy Pad SMD T/R")
      (fields
        (field (name "MANUFACTURER") "Yageo")
        (field (name "MANUFACTURER PART NUMBER") "RC0805FR-0710KL")
      )
      (libsource (lib "Smart_Podium") (part "RC0805FR-0710KL"))
    )
    (comp (ref "R36")
      (value "10K")
      (footprint "R0805")
      (description "Res Thick Film 0805 10K Ohm 1% 0.125W(1/8W) +/-100ppm/C Epoxy Pad SMD T/R")
      (fields
        (field (name "MANUFACTURER") "Yageo")
        (field (name "MANUFACTURER PART NUMBER") "RC0805FR-0710KL")
      )
      (libsource (lib "Smart_Podium") (part "RC0805FR-0710KL"))
    )
    (comp (ref "R37")
      (value "10K")
      (footprint "R0805")
      (description "Res Thick Film 0805 10K Ohm 1% 0.125W(1/8W) +/-100ppm/C Epoxy Pad SMD T/R")
      (fields
        (field (name "MANUFACTURER") "Yageo")
        (field (name "MANUFACTURER PART NUMBER") "RC0805FR-0710KL")
      )
      (libsource (lib "Smart_Podium") (part "RC0805FR-0710KL"))
    )
    (comp (ref "R38")
      (value "560R")
      (footprint "R0805")
      (description "Res General Purpose Thick Film 0805 560 Ohm 1% 1/8W ±100ppm/°C Molded Paper T/R")
      (fields
        (field (name "MANUFACTURER") "Yageo")
        (field (name "MANUFACTURER PART NUMBER") "RC0805FR-07560RL")
      )
      (libsource (lib "Smart_Podium") (part "RC0805FR-07560RL"))
    )
    (comp (ref "R39")
      (value "560R")
      (footprint "R0805")
      (description "Res General Purpose Thick Film 0805 560 Ohm 1% 1/8W ±100ppm/°C Molded Paper T/R")
      (fields
        (field (name "MANUFACTURER") "Yageo")
        (field (name "MANUFACTURER PART NUMBER") "RC0805FR-07560RL")
      )
      (libsource (lib "Smart_Podium") (part "RC0805FR-07560RL"))
    )
    (comp (ref "R40")
      (value "560R")
      (footprint "R0805")
      (description "Res General Purpose Thick Film 0805 560 Ohm 1% 1/8W ±100ppm/°C Molded Paper T/R")
      (fields
        (field (name "MANUFACTURER") "Yageo")
        (field (name "MANUFACTURER PART NUMBER") "RC0805FR-07560RL")
      )
      (libsource (lib "Smart_Podium") (part "RC0805FR-07560RL"))
    )
    (comp (ref "R41")
      (value "560R")
      (footprint "R0805")
      (description "Res General Purpose Thick Film 0805 560 Ohm 1% 1/8W ±100ppm/°C Molded Paper T/R")
      (fields
        (field (name "MANUFACTURER") "Yageo")
        (field (name "MANUFACTURER PART NUMBER") "RC0805FR-07560RL")
      )
      (libsource (lib "Smart_Podium") (part "RC0805FR-07560RL"))
    )
    (comp (ref "R42")
      (value "560R")
      (footprint "R0805")
      (description "Res General Purpose Thick Film 0805 560 Ohm 1% 1/8W ±100ppm/°C Molded Paper T/R")
      (fields
        (field (name "MANUFACTURER") "Yageo")
        (field (name "MANUFACTURER PART NUMBER") "RC0805FR-07560RL")
      )
      (libsource (lib "Smart_Podium") (part "RC0805FR-07560RL"))
    )
    (comp (ref "SW1")
      (value "1825910-6")
      (footprint "1825910-6")
      (description "Switch Tactile OFF (ON) SPST Round Button PC Pins 0.05A 24VDC 1.57N Thru-Hole Loose")
      (fields (field (name "MANUFACTURER") "TE Connectivity Alcoswitch"))
      (libsource (lib "20Pin_Arduino_Project_V1I1") (part "1825910-6"))
    )
    (comp (ref "SW2")
      (value "1825910-6")
      (footprint "1825910-6")
      (description "Switch Tactile OFF (ON) SPST Round Button PC Pins 0.05A 24VDC 1.57N Thru-Hole Loose")
      (fields (field (name "MANUFACTURER") "TE Connectivity Alcoswitch"))
      (libsource (lib "20Pin_Arduino_Project_V1I1") (part "1825910-6"))
    )
    (comp (ref "U1")
      (value "LTV-817S")
      (footprint "LTST-LTV-817S-4_V")
      (description "Photocoupler - Phototransistor Output, 35 V VCEO, -50 to 110 degC, 4-Pin SMD, RoHS, Tape and Reel")
      (fields (field (name "MANUFACTURER") "Lite-On"))
      (libsource (lib "Smart_Podium") (part "LTV-817S"))
    )
    (comp (ref "U2")
      (value "LTV-817S")
      (footprint "LTST-LTV-817S-4_V")
      (description "Photocoupler - Phototransistor Output, 35 V VCEO, -50 to 110 degC, 4-Pin SMD, RoHS, Tape and Reel")
      (fields (field (name "MANUFACTURER") "Lite-On"))
      (libsource (lib "Smart_Podium") (part "LTV-817S"))
    )
    (comp (ref "U3")
      (value "LTV-817S")
      (footprint "LTST-LTV-817S-4_V")
      (description "Photocoupler - Phototransistor Output, 35 V VCEO, -50 to 110 degC, 4-Pin SMD, RoHS, Tape and Reel")
      (fields (field (name "MANUFACTURER") "Lite-On"))
      (libsource (lib "Smart_Podium") (part "LTV-817S"))
    )
    (comp (ref "U4")
      (value "LTV-817S")
      (footprint "LTST-LTV-817S-4_V")
      (description "Photocoupler - Phototransistor Output, 35 V VCEO, -50 to 110 degC, 4-Pin SMD, RoHS, Tape and Reel")
      (fields (field (name "MANUFACTURER") "Lite-On"))
      (libsource (lib "Smart_Podium") (part "LTV-817S"))
    )
    (comp (ref "U5")
      (value "ESP32-WROOM-32E-H4")
      (footprint "XCVR_ESP32-WROOM-32E_(4MB_HIGH_TEMP)")
      (description "Rx Txrx Mod Wifi Trace Ant SMD")
      (fields (field (name "MANUFACTURER") "Espressif Systems"))
      (libsource (lib "Smart_Podium") (part "ESP32-WROOM-32E-H4"))
    )
    (comp (ref "U6")
      (value "AP63203WU-7")
      (footprint "FP-TSOT26-MFG")
      (description "AP63203 Series 3.3 V 2 A SMT Fixed Low IQ Synchronous Buck - TSOT-26")
      (fields (field (name "MANUFACTURER") "Diodes"))
      (libsource (lib "Smart_Podium") (part "AP63203WU-7"))
    )
    (comp (ref "U7")
      (value "AP63205WU-7")
      (footprint "FP-TSOT26-MFG")
      (description "AP63205 Series 32 V 2 A 1.1 MHz Synchronous Buck Converter -TSOT-26")
      (fields (field (name "MANUFACTURER") "Diodes"))
      (libsource (lib "Smart_Podium") (part "AP63205WU-7"))
    )
    (comp (ref "U8")
      (value "MMPQ3904")
      (footprint "16SOIC")
      (description "MMPQ39 Series NPN 1 W 40 V 200 mA General Purpose Transistor - SOIC-16")
      (fields (field (name "MANUFACTURER") "ON Semiconductor / Fairchild"))
      (libsource (lib "Smart_Podium") (part "MMPQ3904"))
    )
    (comp (ref "U9")
      (value "MMPQ3904")
      (footprint "16SOIC")
      (description "MMPQ39 Series NPN 1 W 40 V 200 mA General Purpose Transistor - SOIC-16")
      (fields (field (name "MANUFACTURER") "ON Semiconductor / Fairchild"))
      (libsource (lib "Smart_Podium") (part "MMPQ3904"))
    )
    (comp (ref "U10")
      (value "DC-DC 5V-5V")
      (footprint "DC-DC isolator 1x4 pins")
      (description "1W, i/p: 4.5V ~ 5.5V, single o/p: 5V, SIP")
      (fields (field (name "MANUFACTURER") "MORNSUN") (field (name "MANUFACTURER PART NUMBER") "B0505S-1WR3"))
      (libsource (lib "Smart_Podium") (part "B0505S-1WR3"))
    )
  )
  (nets
    (net (code "1") (name "+3V3") (class "Default")
      (node (ref "C12") (pin "2") (pinfunction "2_2") (pintype "passive"))
      (node (ref "C13") (pin "2") (pinfunction "2_2") (pintype "passive"))
      (node (ref "C2") (pin "2") (pinfunction "2_2") (pintype "passive"))
      (node (ref "C3") (pin "1") (pinfunction "1_1") (pintype "passive"))
      (node (ref "J7") (pin "2") (pinfunction "2_2") (pintype "passive"))
      (node (ref "J8") (pin "3") (pinfunction "3_3") (pintype "passive"))
      (node (ref "L2") (pin "2") (pinfunction "2_2") (pintype "passive"))
      (node (ref "R13") (pin "2") (pinfunction "2_2") (pintype "passive"))
      (node (ref "R29") (pin "2") (pinfunction "2_2") (pintype "passive"))
      (node (ref "R9") (pin "1") (pinfunction "1_1") (pintype "passive"))
      (node (ref "U5") (pin "2") (pinfunction "3V3_2") (pintype "power_in"))
      (node (ref "U6") (pin "1") (pinfunction "FB_1") (pintype "input"))
    )
    (net (code "2") (name "+5V") (class "Default")
      (node (ref "C14") (pin "2") (pinfunction "2_2") (pintype "passive"))
      (node (ref "C15") (pin "2") (pinfunction "2_2") (pintype "passive"))
      (node (ref "C16") (pin "2") (pinfunction "2_2") (pintype "passive"))
      (node (ref "J7") (pin "1") (pinfunction "1_1") (pintype "passive"))
      (node (ref "L3") (pin "2") (pinfunction "2_2") (pintype "passive"))
      (node (ref "L4") (pin "1") (pinfunction "1_1") (pintype "passive"))
      (node (ref "R28") (pin "2") (pinfunction "2_2") (pintype "passive"))
      (node (ref "U1") (pin "1") (pinfunction "ANODE_1") (pintype "passive"))
      (node (ref "U2") (pin "1") (pinfunction "ANODE_1") (pintype "passive"))
      (node (ref "U3") (pin "1") (pinfunction "ANODE_1") (pintype "passive"))
      (node (ref "U4") (pin "1") (pinfunction "ANODE_1") (pintype "passive"))
      (node (ref "U7") (pin "1") (pinfunction "FB_1") (pintype "input"))
    )
    (net (code "3") (name "+5V_Relay") (class "Default")
      (node (ref "C18") (pin "2") (pinfunction "2_2") (pintype "passive"))
      (node (ref "D1") (pin "1") (pinfunction "Cathode_1") (pintype "passive"))
      (node (ref "D2") (pin "1") (pinfunction "Cathode_1") (pintype "passive"))
      (node (ref "D3") (pin "1") (pinfunction "Cathode_1") (pintype "passive"))
      (node (ref "D4") (pin "1") (pinfunction "Cathode_1") (pintype "passive"))
      (node (ref "K1") (pin "1") (pinfunction "1_1") (pintype "passive"))
      (node (ref "K2") (pin "1") (pinfunction "1_1") (pintype "passive"))
      (node (ref "K3") (pin "1") (pinfunction "1_1") (pintype "passive"))
      (node (ref "K4") (pin "1") (pinfunction "1_1") (pintype "passive"))
      (node (ref "R38") (pin "2") (pinfunction "2_2") (pintype "passive"))
      (node (ref "R39") (pin "2") (pinfunction "2_2") (pintype "passive"))
      (node (ref "R40") (pin "2") (pinfunction "2_2") (pintype "passive"))
      (node (ref "R41") (pin "2") (pinfunction "2_2") (pintype "passive"))
      (node (ref "U1") (pin "4") (pinfunction "COLLECTOR_4") (pintype "passive"))
      (node (ref "U10") (pin "4") (pinfunction "+Vo_4") (pintype "passive"))
      (node (ref "U2") (pin "4") (pinfunction "COLLECTOR_4") (pintype "passive"))
      (node (ref "U3") (pin "4") (pinfunction "COLLECTOR_4") (pintype "passive"))
      (node (ref "U4") (pin "4") (pinfunction "COLLECTOR_4") (pintype "passive"))
    )
    (net (code "4") (name "+12V") (class "Default")
      (node (ref "C4") (pin "2") (pinfunction "2_2") (pintype "passive"))
      (node (ref "C6") (pin "1") (pinfunction "1_1") (pintype "passive"))
      (node (ref "C9") (pin "2") (pinfunction "2_2") (pintype "passive"))
      (node (ref "L1") (pin "2") (pinfunction "2_2") (pintype "passive"))
      (node (ref "U6") (pin "2") (pinfunction "EN_2") (pintype "input"))
      (node (ref "U6") (pin "3") (pinfunction "VIN_3") (pintype "power_in"))
      (node (ref "U7") (pin "2") (pinfunction "EN_2") (pintype "input"))
      (node (ref "U7") (pin "3") (pinfunction "VIN_3") (pintype "power_in"))
    )
    (net (code "5") (name "+12V_JACK") (class "Default")
      (node (ref "C5") (pin "1") (pinfunction "1_1") (pintype "passive"))
      (node (ref "J6") (pin "1") (pinfunction "1_1") (pintype "passive"))
      (node (ref "L1") (pin "1") (pinfunction "1_1") (pintype "passive"))
    )
    (net (code "6") (name "/5V_in") (class "Default")
      (node (ref "C17") (pin "2") (pinfunction "2_2") (pintype "passive"))
      (node (ref "L4") (pin "2") (pinfunction "2_2") (pintype "passive"))
      (node (ref "U10") (pin "2") (pinfunction "Vin_2") (pintype "passive"))
    )
    (net (code "7") (name "/BTN1") (class "Default")
      (node (ref "J7") (pin "3") (pinfunction "3_3") (pintype "passive"))
      (node (ref "U5") (pin "24") (pinfunction "IO2_24") (pintype "bidirectional"))
    )
    (net (code "8") (name "/BTN2") (class "Default")
      (node (ref "J7") (pin "4") (pinfunction "4_4") (pintype "passive"))
      (node (ref "U5") (pin "26") (pinfunction "IO4_26") (pintype "bidirectional"))
    )
    (net (code "9") (name "/BTN3") (class "Default")
      (node (ref "J7") (pin "5") (pinfunction "5_5") (pintype "passive"))
      (node (ref "U5") (pin "29") (pinfunction "IO5_29") (pintype "bidirectional"))
    )
    (net (code "10") (name "/BTN4") (class "Default")
      (node (ref "J7") (pin "6") (pinfunction "6_6") (pintype "passive"))
      (node (ref "U5") (pin "6") (pinfunction "IO34_6") (pintype "input"))
    )
    (net (code "11") (name "/BUCK3V3_BST") (class "Default")
      (node (ref "C10") (pin "2") (pinfunction "2_2") (pintype "passive"))
      (node (ref "U6") (pin "6") (pinfunction "BST_6") (pintype "input"))
    )
    (net (code "12") (name "/BUCK3V3_SW") (class "Default")
      (node (ref "C10") (pin "1") (pinfunction "1_1") (pintype "passive"))
      (node (ref "L2") (pin "1") (pinfunction "1_1") (pintype "passive"))
      (node (ref "U6") (pin "5") (pinfunction "SW_5") (pintype "power_in"))
    )
    (net (code "13") (name "/BUCK5V_BST") (class "Default")
      (node (ref "C11") (pin "2") (pinfunction "2_2") (pintype "passive"))
      (node (ref "U7") (pin "6") (pinfunction "BST_6") (pintype "input"))
    )
    (net (code "14") (name "/BUCK5V_SW") (class "Default")
      (node (ref "C11") (pin "1") (pinfunction "1_1") (pintype "passive"))
      (node (ref "L3") (pin "1") (pinfunction "1_1") (pintype "passive"))
      (node (ref "U7") (pin "5") (pinfunction "SW_5") (pintype "power_in"))
    )
    (net (code "15") (name "/BUTTON_BOOT") (class "Default")
      (node (ref "R10") (pin "2") (pinfunction "2_2") (pintype "passive"))
      (node (ref "U5") (pin "25") (pinfunction "IO0_25") (pintype "bidirectional"))
    )
    (net (code "16") (name "/BUTTON_BOOT_n") (class "Default")
      (node (ref "C7") (pin "2") (pinfunction "2_2") (pintype "passive"))
      (node (ref "R10") (pin "1") (pinfunction "1_1") (pintype "passive"))
      (node (ref "SW1") (pin "1") (pinfunction "1_1") (pintype "passive"))
      (node (ref "SW1") (pin "2") (pinfunction "2_2") (pintype "passive"))
    )
    (net (code "17") (name "/BUTTON_EN") (class "Default")
      (node (ref "C1") (pin "2") (pinfunction "2_2") (pintype "passive"))
      (node (ref "R11") (pin "2") (pinfunction "2_2") (pintype "passive"))
      (node (ref "R9") (pin "2") (pinfunction "2_2") (pintype "passive"))
      (node (ref "U5") (pin "3") (pinfunction "EN_3") (pintype "input"))
    )
    (net (code "18") (name "/BUTTON_EN_n") (class "Default")
      (node (ref "C8") (pin "2") (pinfunction "2_2") (pintype "passive"))
      (node (ref "R11") (pin "1") (pinfunction "1_1") (pintype "passive"))
      (node (ref "SW2") (pin "1") (pinfunction "1_1") (pintype "passive"))
      (node (ref "SW2") (pin "2") (pinfunction "2_2") (pintype "passive"))
    )
    (net (code "19") (name "/CTS") (class "Default")
      (node (ref "J8") (pin "2") (pinfunction "2_2") (pintype "passive+no_connect"))
    )
    (net (code "20") (name "/Coll_Q1") (class "Default")
      (node (ref "D1") (pin "2") (pinfunction "Anode_2") (pintype "passive"))
      (node (ref "D10") (pin "1") (pinfunction "Cathode_1") (pintype "passive"))
      (node (ref "K1") (pin "4") (pinfunction "4_4") (pintype "passive"))
      (node (ref "Q1") (pin "3") (pinfunction "C_3") (pintype "passive"))
    )
    (net (code "21") (name "/Coll_Q2") (class "Default")
      (node (ref "D2") (pin "2") (pinfunction "Anode_2") (pintype "passive"))
      (node (ref "D9") (pin "1") (pinfunction "Cathode_1") (pintype "passive"))
      (node (ref "K2") (pin "4") (pinfunction "4_4") (pintype "passive"))
      (node (ref "Q2") (pin "3") (pinfunction "C_3") (pintype "passive"))
    )
    (net (code "22") (name "/Coll_Q3") (class "Default")
      (node (ref "D3") (pin "2") (pinfunction "Anode_2") (pintype "passive"))
      (node (ref "D8") (pin "1") (pinfunction "Cathode_1") (pintype "passive"))
      (node (ref "K3") (pin "4") (pinfunction "4_4") (pintype "passive"))
      (node (ref "Q3") (pin "3") (pinfunction "C_3") (pintype "passive"))
    )
    (net (code "23") (name "/Coll_Q4") (class "Default")
      (node (ref "D4") (pin "2") (pinfunction "Anode_2") (pintype "passive"))
      (node (ref "D7") (pin "1") (pinfunction "Cathode_1") (pintype "passive"))
      (node (ref "K4") (pin "4") (pinfunction "4_4") (pintype "passive"))
      (node (ref "Q4") (pin "3") (pinfunction "C_3") (pintype "passive"))
    )
    (net (code "24") (name "/DTR") (class "Default")
      (node (ref "J8") (pin "6") (pinfunction "6_6") (pintype "passive+no_connect"))
    )
    (net (code "25") (name "/IO12") (class "Default")
      (node (ref "R12") (pin "1") (pinfunction "1_1") (pintype "passive"))
      (node (ref "U5") (pin "14") (pinfunction "IO12_14") (pintype "bidirectional"))
    )
    (net (code "26") (name "/IO16") (class "Default")
      (node (ref "R13") (pin "1") (pinfunction "1_1") (pintype "passive"))
      (node (ref "U5") (pin "27") (pinfunction "IO16_27") (pintype "bidirectional"))
    )
    (net (code "27") (name "/IO17") (class "Default")
      (node (ref "R18") (pin "1") (pinfunction "1_1") (pintype "passive"))
      (node (ref "R37") (pin "1") (pinfunction "1_1") (pintype "passive"))
      (node (ref "U5") (pin "28") (pinfunction "IO17_28") (pintype "bidirectional"))
    )
    (net (code "28") (name "/IO18") (class "Default")
      (node (ref "R19") (pin "1") (pinfunction "1_1") (pintype "passive"))
      (node (ref "R36") (pin "1") (pinfunction "1_1") (pintype "passive"))
      (node (ref "U5") (pin "30") (pinfunction "IO18_30") (pintype "bidirectional"))
    )
    (net (code "29") (name "/IO19") (class "Default")
      (node (ref "R20") (pin "1") (pinfunction "1_1") (pintype "passive"))
      (node (ref "R35") (pin "1") (pinfunction "1_1") (pintype "passive"))
      (node (ref "U5") (pin "31") (pinfunction "IO19_31") (pintype "bidirectional"))
    )
    (net (code "30") (name "/IO21") (class "Default")
      (node (ref "R21") (pin "1") (pinfunction "1_1") (pintype "passive"))
      (node (ref "R34") (pin "1") (pinfunction "1_1") (pintype "passive"))
      (node (ref "U5") (pin "33") (pinfunction "IO21_33") (pintype "bidirectional"))
    )
    (net (code "31") (name "/IO22") (class "Default")
      (node (ref "R17") (pin "1") (pinfunction "1_1") (pintype "passive"))
      (node (ref "R30") (pin "1") (pinfunction "1_1") (pintype "passive"))
      (node (ref "U5") (pin "36") (pinfunction "IO22_36") (pintype "bidirectional"))
    )
    (net (code "32") (name "/IO23") (class "Default")
      (node (ref "R16") (pin "1") (pinfunction "1_1") (pintype "passive"))
      (node (ref "R31") (pin "1") (pinfunction "1_1") (pintype "passive"))
      (node (ref "U5") (pin "37") (pinfunction "IO23_37") (pintype "bidirectional"))
    )
    (net (code "33") (name "/IO25") (class "Default")
      (node (ref "R15") (pin "1") (pinfunction "1_1") (pintype "passive"))
      (node (ref "R32") (pin "1") (pinfunction "1_1") (pintype "passive"))
      (node (ref "U5") (pin "10") (pinfunction "IO25_10") (pintype "bidirectional"))
    )
    (net (code "34") (name "/IO26") (class "Default")
      (node (ref "R14") (pin "1") (pinfunction "1_1") (pintype "passive"))
      (node (ref "R33") (pin "1") (pinfunction "1_1") (pintype "passive"))
      (node (ref "U5") (pin "11") (pinfunction "IO26_11") (pintype "bidirectional"))
    )
    (net (code "35") (name "/IO27") (class "Default")
      (node (ref "R26") (pin "1") (pinfunction "1_1") (pintype "passive"))
      (node (ref "U5") (pin "12") (pinfunction "IO27_12") (pintype "bidirectional"))
    )
    (net (code "36") (name "/IRBaseQ") (class "Default")
      (node (ref "Q5") (pin "1") (pinfunction "B_1") (pintype "passive"))
      (node (ref "R26") (pin "2") (pinfunction "2_2") (pintype "passive"))
    )
    (net (code "37") (name "/IRLED") (class "Default")
      (node (ref "J7") (pin "11") (pinfunction "11_11") (pintype "passive"))
      (node (ref "R27") (pin "2") (pinfunction "2_2") (pintype "passive"))
    )
    (net (code "38") (name "/LBaseQ1") (class "Default")
      (node (ref "R14") (pin "2") (pinfunction "2_2") (pintype "passive"))
      (node (ref "U8") (pin "15") (pinfunction "15_15") (pintype "passive"))
    )
    (net (code "39") (name "/LBaseQ2") (class "Default")
      (node (ref "R15") (pin "2") (pinfunction "2_2") (pintype "passive"))
      (node (ref "U8") (pin "13") (pinfunction "13_13") (pintype "passive"))
    )
    (net (code "40") (name "/LBaseQ3") (class "Default")
      (node (ref "R16") (pin "2") (pinfunction "2_2") (pintype "passive"))
      (node (ref "U8") (pin "11") (pinfunction "11_11") (pintype "passive"))
    )
    (net (code "41") (name "/LBaseQ4") (class "Default")
      (node (ref "R17") (pin "2") (pinfunction "2_2") (pintype "passive"))
      (node (ref "U8") (pin "9") (pinfunction "9_9") (pintype "passive"))
    )
    (net (code "42") (name "/LEDCollQ1") (class "Default")
      (node (ref "J7") (pin "10") (pinfunction "10_10") (pintype "passive"))
      (node (ref "R22") (pin "2") (pinfunction "2_2") (pintype "passive"))
    )
    (net (code "43") (name "/LEDCollQ2") (class "Default")
      (node (ref "J7") (pin "9") (pinfunction "9_9") (pintype "passive"))
      (node (ref "R23") (pin "2") (pinfunction "2_2") (pintype "passive"))
    )
    (net (code "44") (name "/LEDCollQ3") (class "Default")
      (node (ref "J7") (pin "8") (pinfunction "8_8") (pintype "passive"))
      (node (ref "R24") (pin "2") (pinfunction "2_2") (pintype "passive"))
    )
    (net (code "45") (name "/LEDCollQ4") (class "Default")
      (node (ref "J7") (pin "7") (pinfunction "7_7") (pintype "passive"))
      (node (ref "R25") (pin "2") (pinfunction "2_2") (pintype "passive"))
    )
    (net (code "46") (name "/RBaseQ1") (class "Default")
      (node (ref "R21") (pin "2") (pinfunction "2_2") (pintype "passive"))
      (node (ref "U9") (pin "9") (pinfunction "9_9") (pintype "passive"))
    )
    (net (code "47") (name "/RBaseQ2") (class "Default")
      (node (ref "R20") (pin "2") (pinfunction "2_2") (pintype "passive"))
      (node (ref "U9") (pin "11") (pinfunction "11_11") (pintype "passive"))
    )
    (net (code "48") (name "/RBaseQ3") (class "Default")
      (node (ref "R19") (pin "2") (pinfunction "2_2") (pintype "passive"))
      (node (ref "U9") (pin "13") (pinfunction "13_13") (pintype "passive"))
    )
    (net (code "49") (name "/RBaseQ4") (class "Default")
      (node (ref "R18") (pin "2") (pinfunction "2_2") (pintype "passive"))
      (node (ref "U9") (pin "15") (pinfunction "15_15") (pintype "passive"))
    )
    (net (code "50") (name "/RX") (class "Default")
      (node (ref "J8") (pin "5") (pinfunction "5_5") (pintype "passive"))
      (node (ref "U5") (pin "35") (pinfunction "TXD0_35") (pintype "bidirectional"))
    )
    (net (code "51") (name "/Relay1_Out1") (class "Default")
      (node (ref "J1") (pin "2") (pinfunction "2_2") (pintype "passive"))
      (node (ref "K1") (pin "2") (pinfunction "2_2") (pintype "passive"))
    )
    (net (code "52") (name "/Relay1_Out2") (class "Default")
      (node (ref "J1") (pin "1") (pinfunction "1_1") (pintype "passive"))
      (node (ref "K1") (pin "3") (pinfunction "3_3") (pintype "passive"))
    )
    (net (code "53") (name "/Relay1_Out3") (class "Default")
      (node (ref "J1") (pin "3") (pinfunction "3_3") (pintype "passive"))
      (node (ref "K1") (pin "5") (pinfunction "5_5") (pintype "passive"))
    )
    (net (code "54") (name "/Relay2_Out1") (class "Default")
      (node (ref "J2") (pin "2") (pinfunction "2_2") (pintype "passive"))
      (node (ref "K2") (pin "2") (pinfunction "2_2") (pintype "passive"))
    )
    (net (code "55") (name "/Relay2_Out2") (class "Default")
      (node (ref "J2") (pin "1") (pinfunction "1_1") (pintype "passive"))
      (node (ref "K2") (pin "3") (pinfunction "3_3") (pintype "passive"))
    )
    (net (code "56") (name "/Relay2_Out3") (class "Default")
      (node (ref "J2") (pin "3") (pinfunction "3_3") (pintype "passive"))
      (node (ref "K2") (pin "5") (pinfunction "5_5") (pintype "passive"))
    )
    (net (code "57") (name "/Relay3_Out1") (class "Default")
      (node (ref "J3") (pin "2") (pinfunction "2_2") (pintype "passive"))
      (node (ref "K3") (pin "2") (pinfunction "2_2") (pintype "passive"))
    )
    (net (code "58") (name "/Relay3_Out2") (class "Default")
      (node (ref "J3") (pin "1") (pinfunction "1_1") (pintype "passive"))
      (node (ref "K3") (pin "3") (pinfunction "3_3") (pintype "passive"))
    )
    (net (code "59") (name "/Relay3_Out3") (class "Default")
      (node (ref "J3") (pin "3") (pinfunction "3_3") (pintype "passive"))
      (node (ref "K3") (pin "5") (pinfunction "5_5") (pintype "passive"))
    )
    (net (code "60") (name "/Relay4_Out1") (class "Default")
      (node (ref "J4") (pin "2") (pinfunction "2_2") (pintype "passive"))
      (node (ref "K4") (pin "2") (pinfunction "2_2") (pintype "passive"))
    )
    (net (code "61") (name "/Relay4_Out2") (class "Default")
      (node (ref "J4") (pin "1") (pinfunction "1_1") (pintype "passive"))
      (node (ref "K4") (pin "3") (pinfunction "3_3") (pintype "passive"))
    )
    (net (code "62") (name "/Relay4_Out3") (class "Default")
      (node (ref "J4") (pin "3") (pinfunction "3_3") (pintype "passive"))
      (node (ref "K4") (pin "5") (pinfunction "5_5") (pintype "passive"))
    )
    (net (code "63") (name "/RelayInp1") (class "Default")
      (node (ref "R1") (pin "1") (pinfunction "1_1") (pintype "passive"))
      (node (ref "U9") (pin "7") (pinfunction "7_7") (pintype "passive"))
      (node (ref "U9") (pin "8") (pinfunction "8_8") (pintype "passive"))
    )
    (net (code "64") (name "/RelayInp2") (class "Default")
      (node (ref "R3") (pin "1") (pinfunction "1_1") (pintype "passive"))
      (node (ref "U9") (pin "5") (pinfunction "5_5") (pintype "passive"))
      (node (ref "U9") (pin "6") (pinfunction "6_6") (pintype "passive"))
    )
    (net (code "65") (name "/RelayInp3") (class "Default")
      (node (ref "R5") (pin "1") (pinfunction "1_1") (pintype "passive"))
      (node (ref "U9") (pin "3") (pinfunction "3_3") (pintype "passive"))
      (node (ref "U9") (pin "4") (pinfunction "4_4") (pintype "passive"))
    )
    (net (code "66") (name "/RelayInp4") (class "Default")
      (node (ref "R7") (pin "1") (pinfunction "1_1") (pintype "passive"))
      (node (ref "U9") (pin "1") (pinfunction "C1_1") (pintype "passive"))
      (node (ref "U9") (pin "2") (pinfunction "2_2") (pintype "passive"))
    )
    (net (code "67") (name "/TX") (class "Default")
      (node (ref "J8") (pin "4") (pinfunction "4_4") (pintype "passive"))
      (node (ref "U5") (pin "34") (pinfunction "RXD0_34") (pintype "bidirectional"))
    )
    (net (code "68") (name "/USER_LED") (class "Default")
      (node (ref "R42") (pin "2") (pinfunction "2_2") (pintype "passive"))
      (node (ref "U5") (pin "16") (pinfunction "IO13_16") (pintype "bidirectional"))
    )
    (net (code "69") (name "GND") (class "Default")
      (node (ref "C1") (pin "1") (pinfunction "1_1") (pintype "passive"))
      (node (ref "C12") (pin "1") (pinfunction "1_1") (pintype "passive"))
      (node (ref "C13") (pin "1") (pinfunction "1_1") (pintype "passive"))
      (node (ref "C14") (pin "1") (pinfunction "1_1") (pintype "passive"))
      (node (ref "C15") (pin "1") (pinfunction "1_1") (pintype "passive"))
      (node (ref "C16") (pin "1") (pinfunction "1_1") (pintype "passive"))
      (node (ref "C17") (pin "1") (pinfunction "1_1") (pintype "passive"))
      (node (ref "C2") (pin "1") (pinfunction "1_1") (pintype "passive"))
      (node (ref "C3") (pin "2") (pinfunction "2_2") (pintype "passive"))
      (node (ref "C4") (pin "1") (pinfunction "1_1") (pintype "passive"))
      (node (ref "C5") (pin "2") (pinfunction "2_2") (pintype "passive"))
      (node (ref "C6") (pin "2") (pinfunction "2_2") (pintype "passive"))
      (node (ref "C7") (pin "1") (pinfunction "1_1") (pintype "passive"))
      (node (ref "C8") (pin "1") (pinfunction "1_1") (pintype "passive"))
      (node (ref "C9") (pin "1") (pinfunction "1_1") (pintype "passive"))
      (node (ref "D11") (pin "1") (pinfunction "Cathode_1") (pintype "passive"))
      (node (ref "D5") (pin "1") (pinfunction "Cathode_1") (pintype "passive"))
      (node (ref "D6") (pin "1") (pinfunction "Cathode_1") (pintype "passive"))
      (node (ref "J6") (pin "2") (pinfunction "2_2") (pintype "passive"))
      (node (ref "J6") (pin "3") (pinfunction "3_3") (pintype "passive"))
      (node (ref "J7") (pin "12") (pinfunction "12_12") (pintype "passive"))
      (node (ref "J8") (pin "1") (pinfunction "1_1") (pintype "passive"))
      (node (ref "MH1") (pin "1") (pinfunction "1_1") (pintype "passive"))
      (node (ref "MH2") (pin "1") (pinfunction "1_1") (pintype "passive"))
      (node (ref "Q5") (pin "2") (pinfunction "E_2") (pintype "passive"))
      (node (ref "R12") (pin "2") (pinfunction "2_2") (pintype "passive"))
      (node (ref "R30") (pin "2") (pinfunction "2_2") (pintype "passive"))
      (node (ref "R31") (pin "2") (pinfunction "2_2") (pintype "passive"))
      (node (ref "R32") (pin "2") (pinfunction "2_2") (pintype "passive"))
      (node (ref "R33") (pin "2") (pinfunction "2_2") (pintype "passive"))
      (node (ref "R34") (pin "2") (pinfunction "2_2") (pintype "passive"))
      (node (ref "R35") (pin "2") (pinfunction "2_2") (pintype "passive"))
      (node (ref "R36") (pin "2") (pinfunction "2_2") (pintype "passive"))
      (node (ref "R37") (pin "2") (pinfunction "2_2") (pintype "passive"))
      (node (ref "SW1") (pin "3") (pinfunction "3_3") (pintype "passive"))
      (node (ref "SW1") (pin "4") (pinfunction "4_4") (pintype "passive"))
      (node (ref "SW2") (pin "3") (pinfunction "3_3") (pintype "passive"))
      (node (ref "SW2") (pin "4") (pinfunction "4_4") (pintype "passive"))
      (node (ref "U10") (pin "1") (pinfunction "GND_1") (pintype "passive"))
      (node (ref "U5") (pin "1") (pinfunction "GND_1") (pintype "power_in"))
      (node (ref "U5") (pin "15") (pinfunction "GND_15") (pintype "power_in"))
      (node (ref "U5") (pin "38") (pinfunction "GND_38") (pintype "power_in"))
      (node (ref "U5") (pin "39_1") (pinfunction "GND_39_1") (pintype "power_in"))
      (node (ref "U5") (pin "39_2") (pinfunction "GND_39_2") (pintype "power_in"))
      (node (ref "U5") (pin "39_3") (pinfunction "GND_39_3") (pintype "power_in"))
      (node (ref "U5") (pin "39_4") (pinfunction "GND_39_4") (pintype "power_in"))
      (node (ref "U5") (pin "39_5") (pinfunction "GND_39_5") (pintype "power_in"))
      (node (ref "U5") (pin "39_6") (pinfunction "GND_39_6") (pintype "power_in"))
      (node (ref "U5") (pin "39_7") (pinfunction "GND_39_7") (pintype "power_in"))
      (node (ref "U5") (pin "39_8") (pinfunction "GND_39_8") (pintype "power_in"))
      (node (ref "U5") (pin "39_9") (pinfunction "GND_39_9") (pintype "power_in"))
      (node (ref "U6") (pin "4") (pinfunction "GND_4") (pintype "power_in"))
      (node (ref "U7") (pin "4") (pinfunction "GND_4") (pintype "power_in"))
      (node (ref "U8") (pin "10") (pinfunction "10_10") (pintype "passive"))
      (node (ref "U8") (pin "12") (pinfunction "12_12") (pintype "passive"))
      (node (ref "U8") (pin "14") (pinfunction "14_14") (pintype "passive"))
      (node (ref "U8") (pin "16") (pinfunction "16_16") (pintype "passive"))
      (node (ref "U9") (pin "10") (pinfunction "10_10") (pintype "passive"))
      (node (ref "U9") (pin "12") (pinfunction "12_12") (pintype "passive"))
      (node (ref "U9") (pin "14") (pinfunction "14_14") (pintype "passive"))
      (node (ref "U9") (pin "16") (pinfunction "16_16") (pintype "passive"))
    )
    (net (code "70") (name "GND_Relay") (class "Default")
      (node (ref "C18") (pin "1") (pinfunction "1_1") (pintype "passive"))
      (node (ref "Q1") (pin "2") (pinfunction "E_2") (pintype "passive"))
      (node (ref "Q2") (pin "2") (pinfunction "E_2") (pintype "passive"))
      (node (ref "Q3") (pin "2") (pinfunction "E_2") (pintype "passive"))
      (node (ref "Q4") (pin "2") (pinfunction "E_2") (pintype "passive"))
      (node (ref "U10") (pin "3") (pinfunction "0v_3") (pintype "passive"))
    )
    (net (code "71") (name "Net-(D5-Anode)") (class "Default")
      (node (ref "D5") (pin "2") (pinfunction "Anode_2") (pintype "passive"))
      (node (ref "R28") (pin "1") (pinfunction "1_1") (pintype "passive"))
    )
    (net (code "72") (name "Net-(D6-Anode)") (class "Default")
      (node (ref "D6") (pin "2") (pinfunction "Anode_2") (pintype "passive"))
      (node (ref "R29") (pin "1") (pinfunction "1_1") (pintype "passive"))
    )
    (net (code "73") (name "Net-(D7-Anode)") (class "Default")
      (node (ref "D7") (pin "2") (pinfunction "Anode_2") (pintype "passive"))
      (node (ref "R38") (pin "1") (pinfunction "1_1") (pintype "passive"))
    )
    (net (code "74") (name "Net-(D8-Anode)") (class "Default")
      (node (ref "D8") (pin "2") (pinfunction "Anode_2") (pintype "passive"))
      (node (ref "R39") (pin "1") (pinfunction "1_1") (pintype "passive"))
    )
    (net (code "75") (name "Net-(D9-Anode)") (class "Default")
      (node (ref "D9") (pin "2") (pinfunction "Anode_2") (pintype "passive"))
      (node (ref "R40") (pin "1") (pinfunction "1_1") (pintype "passive"))
    )
    (net (code "76") (name "Net-(D10-Anode)") (class "Default")
      (node (ref "D10") (pin "2") (pinfunction "Anode_2") (pintype "passive"))
      (node (ref "R41") (pin "1") (pinfunction "1_1") (pintype "passive"))
    )
    (net (code "77") (name "Net-(D11-Anode)") (class "Default")
      (node (ref "D11") (pin "2") (pinfunction "Anode_2") (pintype "passive"))
      (node (ref "R42") (pin "1") (pinfunction "1_1") (pintype "passive"))
    )
    (net (code "78") (name "Net-(Q1-B)") (class "Default")
      (node (ref "Q1") (pin "1") (pinfunction "B_1") (pintype "passive"))
      (node (ref "R2") (pin "2") (pinfunction "2_2") (pintype "passive"))
    )
    (net (code "79") (name "Net-(Q2-B)") (class "Default")
      (node (ref "Q2") (pin "1") (pinfunction "B_1") (pintype "passive"))
      (node (ref "R4") (pin "2") (pinfunction "2_2") (pintype "passive"))
    )
    (net (code "80") (name "Net-(Q3-B)") (class "Default")
      (node (ref "Q3") (pin "1") (pinfunction "B_1") (pintype "passive"))
      (node (ref "R6") (pin "2") (pinfunction "2_2") (pintype "passive"))
    )
    (net (code "81") (name "Net-(Q4-B)") (class "Default")
      (node (ref "Q4") (pin "1") (pinfunction "B_1") (pintype "passive"))
      (node (ref "R8") (pin "2") (pinfunction "2_2") (pintype "passive"))
    )
    (net (code "82") (name "Net-(Q5-C)") (class "Default")
      (node (ref "Q5") (pin "3") (pinfunction "C_3") (pintype "passive"))
      (node (ref "R27") (pin "1") (pinfunction "1_1") (pintype "passive"))
    )
    (net (code "83") (name "Net-(R23-Pad1)") (class "Default")
      (node (ref "R23") (pin "1") (pinfunction "1_1") (pintype "passive"))
      (node (ref "U8") (pin "3") (pinfunction "3_3") (pintype "passive"))
      (node (ref "U8") (pin "4") (pinfunction "4_4") (pintype "passive"))
    )
    (net (code "84") (name "Net-(R24-Pad1)") (class "Default")
      (node (ref "R24") (pin "1") (pinfunction "1_1") (pintype "passive"))
      (node (ref "U8") (pin "5") (pinfunction "5_5") (pintype "passive"))
      (node (ref "U8") (pin "6") (pinfunction "6_6") (pintype "passive"))
    )
    (net (code "85") (name "Net-(R25-Pad1)") (class "Default")
      (node (ref "R25") (pin "1") (pinfunction "1_1") (pintype "passive"))
      (node (ref "U8") (pin "7") (pinfunction "7_7") (pintype "passive"))
      (node (ref "U8") (pin "8") (pinfunction "8_8") (pintype "passive"))
    )
    (net (code "86") (name "Net-(U1-CATHODE)") (class "Default")
      (node (ref "R1") (pin "2") (pinfunction "2_2") (pintype "passive"))
      (node (ref "U1") (pin "2") (pinfunction "CATHODE_2") (pintype "passive"))
    )
    (net (code "87") (name "Net-(U1-EMITTER)") (class "Default")
      (node (ref "R2") (pin "1") (pinfunction "1_1") (pintype "passive"))
      (node (ref "U1") (pin "3") (pinfunction "EMITTER_3") (pintype "passive"))
    )
    (net (code "88") (name "Net-(U2-CATHODE)") (class "Default")
      (node (ref "R3") (pin "2") (pinfunction "2_2") (pintype "passive"))
      (node (ref "U2") (pin "2") (pinfunction "CATHODE_2") (pintype "passive"))
    )
    (net (code "89") (name "Net-(U2-EMITTER)") (class "Default")
      (node (ref "R4") (pin "1") (pinfunction "1_1") (pintype "passive"))
      (node (ref "U2") (pin "3") (pinfunction "EMITTER_3") (pintype "passive"))
    )
    (net (code "90") (name "Net-(U3-CATHODE)") (class "Default")
      (node (ref "R5") (pin "2") (pinfunction "2_2") (pintype "passive"))
      (node (ref "U3") (pin "2") (pinfunction "CATHODE_2") (pintype "passive"))
    )
    (net (code "91") (name "Net-(U3-EMITTER)") (class "Default")
      (node (ref "R6") (pin "1") (pinfunction "1_1") (pintype "passive"))
      (node (ref "U3") (pin "3") (pinfunction "EMITTER_3") (pintype "passive"))
    )
    (net (code "92") (name "Net-(U4-CATHODE)") (class "Default")
      (node (ref "R7") (pin "2") (pinfunction "2_2") (pintype "passive"))
      (node (ref "U4") (pin "2") (pinfunction "CATHODE_2") (pintype "passive"))
    )
    (net (code "93") (name "Net-(U4-EMITTER)") (class "Default")
      (node (ref "R8") (pin "1") (pinfunction "1_1") (pintype "passive"))
      (node (ref "U4") (pin "3") (pinfunction "EMITTER_3") (pintype "passive"))
    )
    (net (code "94") (name "Net-(U8-C1)") (class "Default")
      (node (ref "R22") (pin "1") (pinfunction "1_1") (pintype "passive"))
      (node (ref "U8") (pin "1") (pinfunction "C1_1") (pintype "passive"))
      (node (ref "U8") (pin "2") (pinfunction "2_2") (pintype "passive"))
    )
    (net (code "95") (name "unconnected-(MH3-Pad1)") (class "Default")
      (node (ref "MH3") (pin "1") (pinfunction "1_1") (pintype "passive+no_connect"))
    )
    (net (code "96") (name "unconnected-(MH4-Pad1)") (class "Default")
      (node (ref "MH4") (pin "1") (pinfunction "1_1") (pintype "passive+no_connect"))
    )
    (net (code "97") (name "unconnected-(U5-IO14-Pad13)") (class "Default")
      (node (ref "U5") (pin "13") (pinfunction "IO14_13") (pintype "bidirectional+no_connect"))
    )
    (net (code "98") (name "unconnected-(U5-IO15-Pad23)") (class "Default")
      (node (ref "U5") (pin "23") (pinfunction "IO15_23") (pintype "bidirectional+no_connect"))
    )
    (net (code "99") (name "unconnected-(U5-IO32-Pad8)") (class "Default")
      (node (ref "U5") (pin "8") (pinfunction "IO32_8") (pintype "bidirectional+no_connect"))
    )
    (net (code "100") (name "unconnected-(U5-IO33-Pad9)") (class "Default")
      (node (ref "U5") (pin "9") (pinfunction "IO33_9") (pintype "bidirectional+no_connect"))
    )
    (net (code "101") (name "unconnected-(U5-IO35-Pad7)") (class "Default")
      (node (ref "U5") (pin "7") (pinfunction "IO35_7") (pintype "input+no_connect"))
    )
    (net (code "102") (name "unconnected-(U5-NC-Pad17)") (class "Default")
      (node (ref "U5") (pin "17") (pinfunction "NC_17") (pintype "passive+no_connect"))
    )
    (net (code "103") (name "unconnected-(U5-NC-Pad18)") (class "Default")
      (node (ref "U5") (pin "18") (pinfunction "NC_18") (pintype "passive+no_connect"))
    )
    (net (code "104") (name "unconnected-(U5-NC-Pad19)") (class "Default")
      (node (ref "U5") (pin "19") (pinfunction "NC_19") (pintype "passive+no_connect"))
    )
    (net (code "105") (name "unconnected-(U5-NC-Pad20)") (class "Default")
      (node (ref "U5") (pin "20") (pinfunction "NC_20") (pintype "passive+no_connect"))
    )
    (net (code "106") (name "unconnected-(U5-NC-Pad21)") (class "Default")
      (node (ref "U5") (pin "21") (pinfunction "NC_21") (pintype "passive+no_connect"))
    )
    (net (code "107") (name "unconnected-(U5-NC-Pad22)") (class "Default")
      (node (ref "U5") (pin "22") (pinfunction "NC_22") (pintype "passive+no_connect"))
    )
    (net (code "108") (name "unconnected-(U5-NC1-Pad32)") (class "Default")
      (node (ref "U5") (pin "32") (pinfunction "NC1_32") (pintype "passive+no_connect"))
    )
    (net (code "109") (name "unconnected-(U5-SENSOR_VN-Pad5)") (class "Default")
      (node (ref "U5") (pin "5") (pinfunction "SENSOR_VN_5") (pintype "input+no_connect"))
    )
    (net (code "110") (name "unconnected-(U5-SENSOR_VP-Pad4)") (class "Default")
      (node (ref "U5") (pin "4") (pinfunction "SENSOR_VP_4") (pintype "input+no_connect"))
    )
  )
)
